# STAC_Test_Board_v1_QSPI.net
KiCad netlist of a schematic drawn in Altium Designer
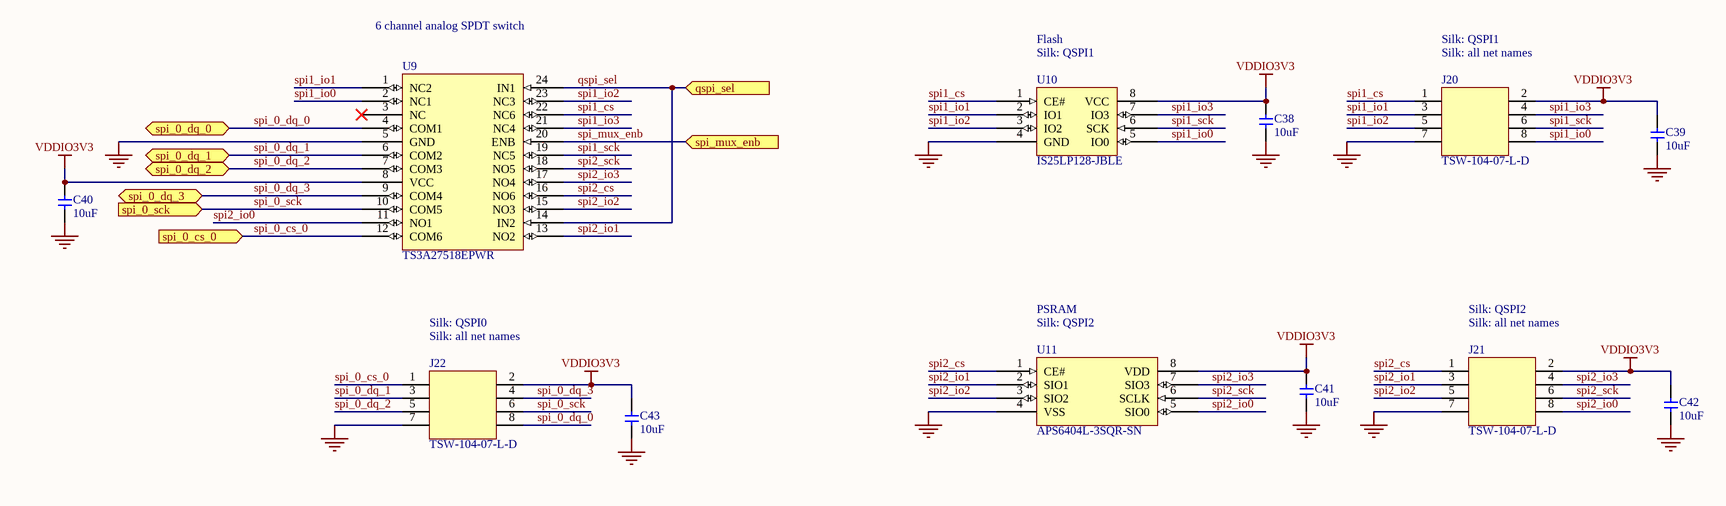
[diagram p0: STAC_Test_Board_v1_QSPI.SchDoc]

(export (version "E")
  (design (tool "Eeschema 10.0.6"))
  (components
    (comp (ref "C38")
      (value "10uF")
      (footprint "BWRC:0603")
      (description "Capacitor generic")
      (libsource (lib "BWRC") (part "DISCRETE_C"))
    )
    (comp (ref "C39")
      (value "10uF")
      (footprint "BWRC:0603")
      (description "Capacitor generic")
      (libsource (lib "BWRC") (part "DISCRETE_C"))
    )
    (comp (ref "C40")
      (value "10uF")
      (footprint "BWRC:0603")
      (description "Capacitor generic")
      (libsource (lib "BWRC") (part "DISCRETE_C"))
    )
    (comp (ref "C41")
      (value "10uF")
      (footprint "BWRC:0603")
      (description "Capacitor generic")
      (libsource (lib "BWRC") (part "DISCRETE_C"))
    )
    (comp (ref "C42")
      (value "10uF")
      (footprint "BWRC:0603")
      (description "Capacitor generic")
      (libsource (lib "BWRC") (part "DISCRETE_C"))
    )
    (comp (ref "C43")
      (value "10uF")
      (footprint "BWRC:0603")
      (description "Capacitor generic")
      (libsource (lib "BWRC") (part "DISCRETE_C"))
    )
    (comp (ref "J20")
      (value "TSW-104-07-L-D")
      (footprint "CON-008-100-400X200/2X4-POST")
      (description "Con 8 pins 2x4")
      (libsource (lib "BWRC") (part "CON_008pin_2x4"))
    )
    (comp (ref "J21")
      (value "TSW-104-07-L-D")
      (footprint "CON-008-100-400X200/2X4-POST")
      (description "Con 8 pins 2x4")
      (libsource (lib "BWRC") (part "CON_008pin_2x4"))
    )
    (comp (ref "J22")
      (value "TSW-104-07-L-D")
      (footprint "CON-008-100-400X200/2X4-POST")
      (description "Con 8 pins 2x4")
      (libsource (lib "BWRC") (part "CON_008pin_2x4"))
    )
    (comp (ref "U9")
      (value "TS3A27518EPWR")
      (footprint "GW-24-.65-6.4")
      (description "Analog switch SPDT 6 channels bidirectional")
      (libsource (lib "BWRC") (part "IC_TS3A27518EPWR"))
    )
    (comp (ref "U10")
      (value "IS25LP128-JBLE")
      (footprint "GW-08-1.27-5.2X8.0")
      (description "Flash memory 128Mb with 133MHz QSPI")
      (libsource (lib "BWRC") (part "IC_IS25LP128"))
    )
    (comp (ref "U11")
      (value "APS6404L-3SQR-SN")
      (footprint "GW-08-1.27-5.0X6.0")
      (description "PSRAM 64Mb with 84-133MHz QSPI, 1024 byte pages")
      (libsource (lib "BWRC") (part "IC_APS6404L"))
    )
  )
  (nets
    (net (code "1") (name "/qspi_sel") (class "Default")
      (node (ref "U9") (pin "14") (pinfunction "IN2_14") (pintype "input"))
      (node (ref "U9") (pin "24") (pinfunction "IN1_24") (pintype "input"))
    )
    (net (code "2") (name "/spi1_cs") (class "Default")
      (node (ref "J20") (pin "1") (pinfunction "1_1") (pintype "passive"))
      (node (ref "U10") (pin "1") (pinfunction "CE#_1") (pintype "input"))
      (node (ref "U9") (pin "22") (pinfunction "NC6_22") (pintype "bidirectional"))
    )
    (net (code "3") (name "/spi1_io0") (class "Default")
      (node (ref "J20") (pin "8") (pinfunction "8_8") (pintype "passive"))
      (node (ref "U10") (pin "5") (pinfunction "IO0_5") (pintype "bidirectional"))
      (node (ref "U9") (pin "2") (pinfunction "NC1_2") (pintype "bidirectional"))
    )
    (net (code "4") (name "/spi1_io1") (class "Default")
      (node (ref "J20") (pin "3") (pinfunction "3_3") (pintype "passive"))
      (node (ref "U10") (pin "2") (pinfunction "IO1_2") (pintype "bidirectional"))
      (node (ref "U9") (pin "1") (pinfunction "NC2_1") (pintype "bidirectional"))
    )
    (net (code "5") (name "/spi1_io2") (class "Default")
      (node (ref "J20") (pin "5") (pinfunction "5_5") (pintype "passive"))
      (node (ref "U10") (pin "3") (pinfunction "IO2_3") (pintype "bidirectional"))
      (node (ref "U9") (pin "23") (pinfunction "NC3_23") (pintype "bidirectional"))
    )
    (net (code "6") (name "/spi1_io3") (class "Default")
      (node (ref "J20") (pin "4") (pinfunction "4_4") (pintype "passive"))
      (node (ref "U10") (pin "7") (pinfunction "IO3_7") (pintype "bidirectional"))
      (node (ref "U9") (pin "21") (pinfunction "NC4_21") (pintype "bidirectional"))
    )
    (net (code "7") (name "/spi1_sck") (class "Default")
      (node (ref "J20") (pin "6") (pinfunction "6_6") (pintype "passive"))
      (node (ref "U10") (pin "6") (pinfunction "SCK_6") (pintype "input"))
      (node (ref "U9") (pin "19") (pinfunction "NC5_19") (pintype "bidirectional"))
    )
    (net (code "8") (name "/spi2_cs") (class "Default")
      (node (ref "J21") (pin "1") (pinfunction "1_1") (pintype "passive"))
      (node (ref "U11") (pin "1") (pinfunction "CE#_1") (pintype "input"))
      (node (ref "U9") (pin "16") (pinfunction "NO6_16") (pintype "bidirectional"))
    )
    (net (code "9") (name "/spi2_io0") (class "Default")
      (node (ref "J21") (pin "8") (pinfunction "8_8") (pintype "passive"))
      (node (ref "U11") (pin "5") (pinfunction "SIO0_5") (pintype "bidirectional"))
      (node (ref "U9") (pin "11") (pinfunction "NO1_11") (pintype "bidirectional"))
    )
    (net (code "10") (name "/spi2_io1") (class "Default")
      (node (ref "J21") (pin "3") (pinfunction "3_3") (pintype "passive"))
      (node (ref "U11") (pin "2") (pinfunction "SIO1_2") (pintype "bidirectional"))
      (node (ref "U9") (pin "13") (pinfunction "NO2_13") (pintype "bidirectional"))
    )
    (net (code "11") (name "/spi2_io2") (class "Default")
      (node (ref "J21") (pin "5") (pinfunction "5_5") (pintype "passive"))
      (node (ref "U11") (pin "3") (pinfunction "SIO2_3") (pintype "bidirectional"))
      (node (ref "U9") (pin "15") (pinfunction "NO3_15") (pintype "bidirectional"))
    )
    (net (code "12") (name "/spi2_io3") (class "Default")
      (node (ref "J21") (pin "4") (pinfunction "4_4") (pintype "passive"))
      (node (ref "U11") (pin "7") (pinfunction "SIO3_7") (pintype "bidirectional"))
      (node (ref "U9") (pin "17") (pinfunction "NO4_17") (pintype "bidirectional"))
    )
    (net (code "13") (name "/spi2_sck") (class "Default")
      (node (ref "J21") (pin "6") (pinfunction "6_6") (pintype "passive"))
      (node (ref "U11") (pin "6") (pinfunction "SCLK_6") (pintype "input"))
      (node (ref "U9") (pin "18") (pinfunction "NO5_18") (pintype "bidirectional"))
    )
    (net (code "14") (name "/spi_0_cs_0") (class "Default")
      (node (ref "J22") (pin "1") (pinfunction "1_1") (pintype "passive"))
      (node (ref "U9") (pin "12") (pinfunction "COM6_12") (pintype "bidirectional"))
    )
    (net (code "15") (name "/spi_0_dq_0") (class "Default")
      (node (ref "J22") (pin "8") (pinfunction "8_8") (pintype "passive"))
      (node (ref "U9") (pin "4") (pinfunction "COM1_4") (pintype "bidirectional"))
    )
    (net (code "16") (name "/spi_0_dq_1") (class "Default")
      (node (ref "J22") (pin "3") (pinfunction "3_3") (pintype "passive"))
      (node (ref "U9") (pin "6") (pinfunction "COM2_6") (pintype "bidirectional"))
    )
    (net (code "17") (name "/spi_0_dq_2") (class "Default")
      (node (ref "J22") (pin "5") (pinfunction "5_5") (pintype "passive"))
      (node (ref "U9") (pin "7") (pinfunction "COM3_7") (pintype "bidirectional"))
    )
    (net (code "18") (name "/spi_0_dq_3") (class "Default")
      (node (ref "J22") (pin "4") (pinfunction "4_4") (pintype "passive"))
      (node (ref "U9") (pin "9") (pinfunction "COM4_9") (pintype "bidirectional"))
    )
    (net (code "19") (name "/spi_0_sck") (class "Default")
      (node (ref "J22") (pin "6") (pinfunction "6_6") (pintype "passive"))
      (node (ref "U9") (pin "10") (pinfunction "COM5_10") (pintype "bidirectional"))
    )
    (net (code "20") (name "/spi_mux_enb") (class "Default")
      (node (ref "U9") (pin "20") (pinfunction "ENB_20") (pintype "input"))
    )
    (net (code "21") (name "GND") (class "Default")
      (node (ref "C38") (pin "2") (pinfunction "2_2") (pintype "passive"))
      (node (ref "C39") (pin "2") (pinfunction "2_2") (pintype "passive"))
      (node (ref "C40") (pin "2") (pinfunction "2_2") (pintype "passive"))
      (node (ref "C41") (pin "2") (pinfunction "2_2") (pintype "passive"))
      (node (ref "C42") (pin "2") (pinfunction "2_2") (pintype "passive"))
      (node (ref "C43") (pin "2") (pinfunction "2_2") (pintype "passive"))
      (node (ref "J20") (pin "7") (pinfunction "7_7") (pintype "passive"))
      (node (ref "J21") (pin "7") (pinfunction "7_7") (pintype "passive"))
      (node (ref "J22") (pin "7") (pinfunction "7_7") (pintype "passive"))
      (node (ref "U10") (pin "4") (pinfunction "GND_4") (pintype "power_in"))
      (node (ref "U11") (pin "4") (pinfunction "VSS_4") (pintype "power_in"))
      (node (ref "U9") (pin "5") (pinfunction "GND_5") (pintype "power_in"))
    )
    (net (code "22") (name "VDDIO3V3") (class "Default")
      (node (ref "C38") (pin "1") (pinfunction "1_1") (pintype "passive"))
      (node (ref "C39") (pin "1") (pinfunction "1_1") (pintype "passive"))
      (node (ref "C40") (pin "1") (pinfunction "1_1") (pintype "passive"))
      (node (ref "C41") (pin "1") (pinfunction "1_1") (pintype "passive"))
      (node (ref "C42") (pin "1") (pinfunction "1_1") (pintype "passive"))
      (node (ref "C43") (pin "1") (pinfunction "1_1") (pintype "passive"))
      (node (ref "J20") (pin "2") (pinfunction "2_2") (pintype "passive"))
      (node (ref "J21") (pin "2") (pinfunction "2_2") (pintype "passive"))
      (node (ref "J22") (pin "2") (pinfunction "2_2") (pintype "passive"))
      (node (ref "U10") (pin "8") (pinfunction "VCC_8") (pintype "power_in"))
      (node (ref "U11") (pin "8") (pinfunction "VDD_8") (pintype "power_in"))
      (node (ref "U9") (pin "8") (pinfunction "VCC_8") (pintype "power_in"))
    )
    (net (code "23") (name "unconnected-(U9-NC-Pad3)") (class "Default")
      (node (ref "U9") (pin "3") (pinfunction "NC_3") (pintype "passive+no_connect"))
    )
  )
)
